# ZNXC.net
KiCad netlist of a schematic drawn in Altium Designer
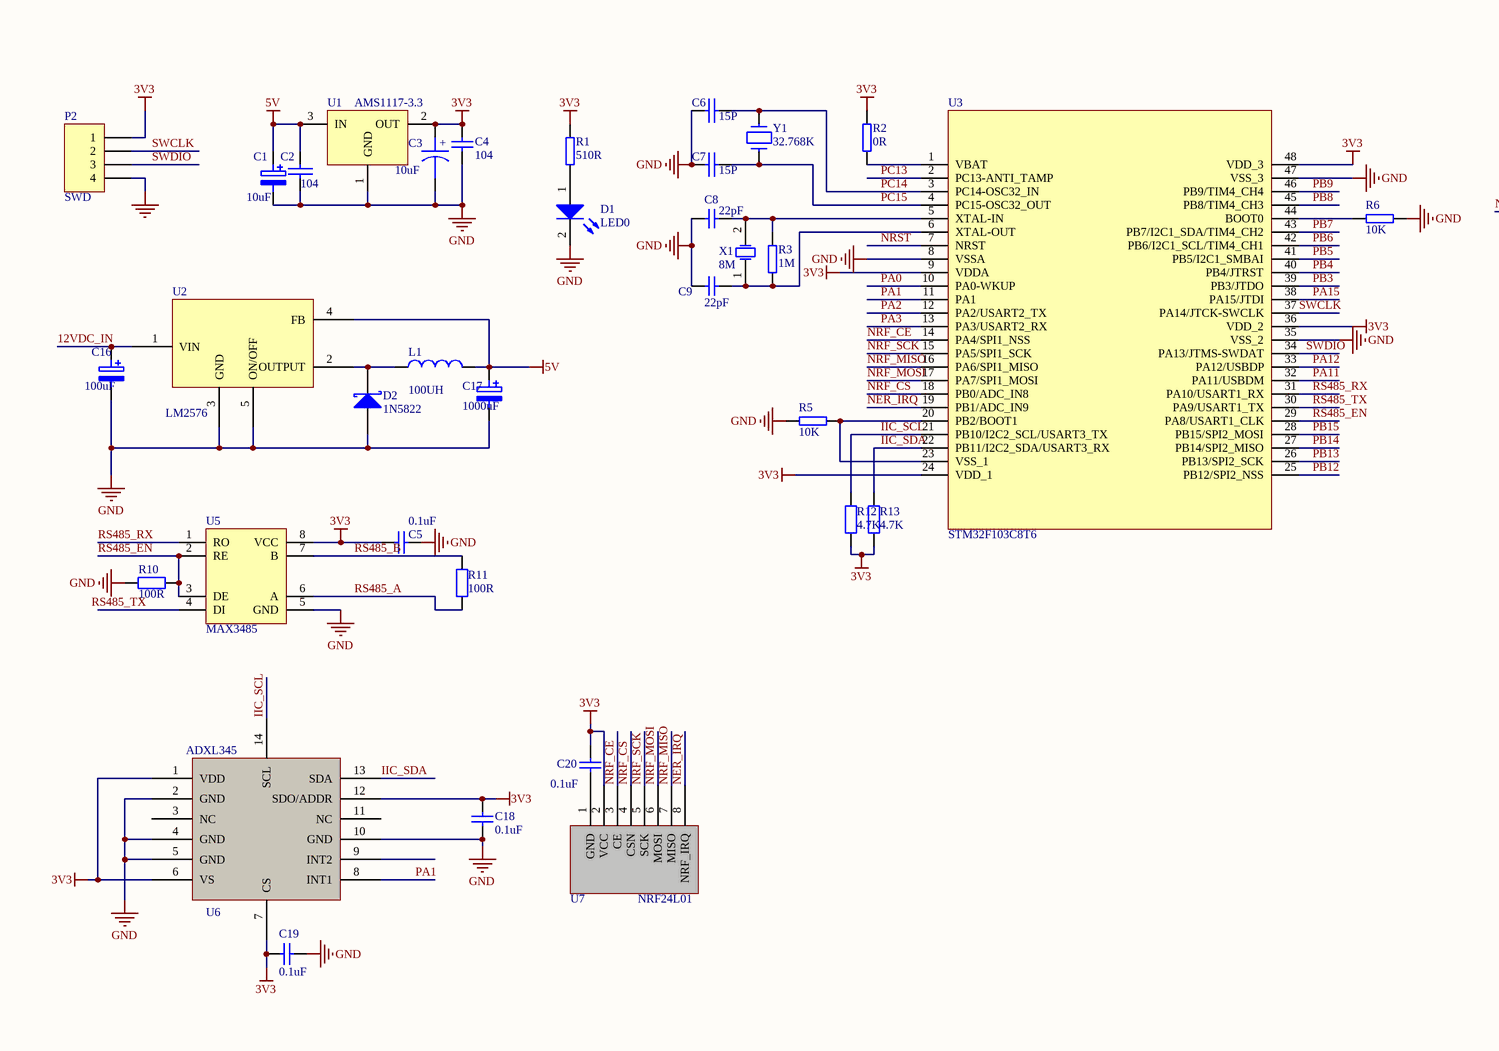
[diagram p0: ZNXC.SchDoc, left]
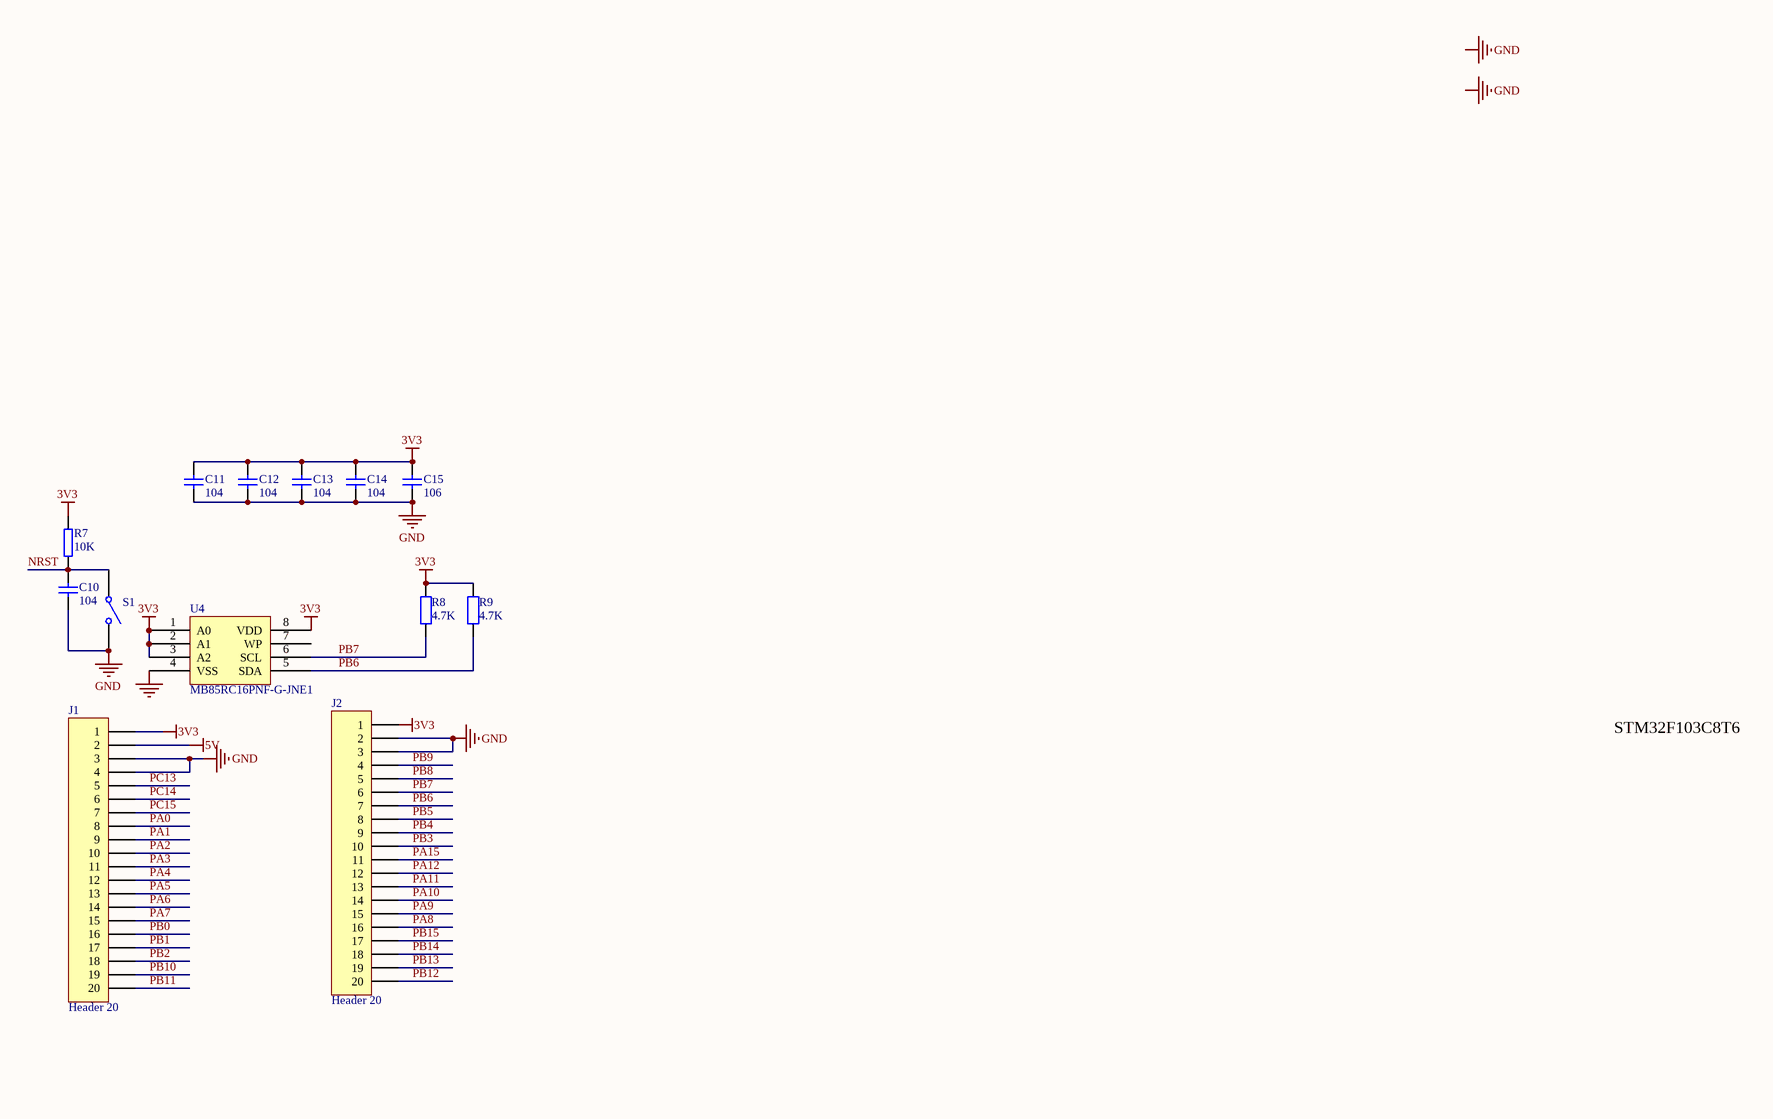
[diagram p1: ZNXC.SchDoc, right]

(export (version "E")
  (design (tool "Eeschema 10.0.6"))
  (components
    (comp (ref "C1") (value "10uF") (footprint "RC0805") (libsource (lib "*") (part "ELECTRO2")))
    (comp (ref "C2")
      (value "104")
      (footprint "RC0603")
      (description "Capacitor")
      (libsource (lib "") (part "CAP_1"))
    )
    (comp (ref "C3")
      (value "10uF")
      (footprint "RC0805")
      (description "Capacitor")
      (libsource (lib "*") (part "CAPACITOR POL"))
    )
    (comp (ref "C4")
      (value "104")
      (footprint "RC0603")
      (description "Capacitor")
      (fields (field (name "PUBLISHER") "Altium Limited"))
      (libsource (lib "*") (part "Cap"))
    )
    (comp (ref "C5")
      (value "0.1uF")
      (footprint "C0603")
      (description "Capacitor")
      (fields (field (name "Comment") "无源贴片电容") (field (name "PUBLISHER") "Altium Limited"))
      (libsource (lib "Miscellaneous Devices") (part "Cap"))
    )
    (comp (ref "C6") (value "15P") (footprint "RC0603") (libsource (lib "*") (part "CAP")))
    (comp (ref "C7") (value "15P") (footprint "RC0603") (libsource (lib "*") (part "CAP")))
    (comp (ref "C8")
      (value "22pF")
      (footprint "RC0603")
      (description "Capacitor")
      (fields (field (name "PUBLISHER") "ZL_A0OFFICE"))
      (libsource (lib "CommomDevices") (part "CAP1"))
    )
    (comp (ref "C9")
      (value "22pF")
      (footprint "RC0603")
      (description "Capacitor")
      (fields (field (name "PUBLISHER") "ZL_A0OFFICE"))
      (libsource (lib "CommomDevices") (part "CAP1"))
    )
    (comp (ref "C10")
      (value "104")
      (footprint "RC0603")
      (description "Capacitor")
      (fields (field (name "PUBLISHER") "ZL_A0OFFICE"))
      (libsource (lib "CommomDevices") (part "CAP1"))
    )
    (comp (ref "C11")
      (value "104")
      (footprint "RC0603")
      (description "Capacitor")
      (fields (field (name "PUBLISHER") "ZL_A0OFFICE"))
      (libsource (lib "CommomDevices") (part "CAP1"))
    )
    (comp (ref "C12")
      (value "104")
      (footprint "RC0603")
      (description "Capacitor")
      (fields (field (name "PUBLISHER") "ZL_A0OFFICE"))
      (libsource (lib "CommomDevices") (part "CAP1"))
    )
    (comp (ref "C13")
      (value "104")
      (footprint "RC0603")
      (description "Capacitor")
      (fields (field (name "PUBLISHER") "ZL_A0OFFICE"))
      (libsource (lib "CommomDevices") (part "CAP1"))
    )
    (comp (ref "C14")
      (value "104")
      (footprint "RC0603")
      (description "Capacitor")
      (fields (field (name "PUBLISHER") "ZL_A0OFFICE"))
      (libsource (lib "CommomDevices") (part "CAP1"))
    )
    (comp (ref "C15")
      (value "106")
      (footprint "RC0805")
      (description "Capacitor")
      (fields (field (name "PUBLISHER") "ZL_A0OFFICE"))
      (libsource (lib "CommomDevices") (part "CAP1"))
    )
    (comp (ref "C16") (value "100uF") (footprint "RC0805") (libsource (lib "*") (part "ELECTRO2")))
    (comp (ref "C17") (value "1000uF") (footprint "RC0805") (libsource (lib "*") (part "ELECTRO2")))
    (comp (ref "C18")
      (value "0.1uF")
      (footprint "C0603")
      (description "Capacitor")
      (fields (field (name "Comment") "无源贴片电容") (field (name "PUBLISHER") "Altium Limited"))
      (libsource (lib "Miscellaneous Devices") (part "Cap"))
    )
    (comp (ref "C19")
      (value "0.1uF")
      (footprint "C0603")
      (description "Capacitor")
      (fields (field (name "Comment") "无源贴片电容") (field (name "PUBLISHER") "Altium Limited"))
      (libsource (lib "Miscellaneous Devices") (part "Cap"))
    )
    (comp (ref "C20")
      (value "0.1uF")
      (footprint "C0603")
      (description "Capacitor")
      (fields (field (name "Comment") "无源贴片电容") (field (name "PUBLISHER") "Altium Limited"))
      (libsource (lib "Miscellaneous Devices") (part "Cap"))
    )
    (comp (ref "D1")
      (value "LED0")
      (footprint "LED0805")
      (description "Typical INFRARED GaAs LED")
      (libsource (lib "Miscellaneous Devices") (part "LED0"))
    )
    (comp (ref "D2")
      (value "1N5822")
      (footprint "DO-204AL")
      (description "Schottky Rectifier")
      (fields (field (name "PUBLISHER") "Altium Limited"))
      (libsource (lib "Miscellaneous Devices") (part "Diode 11DQ03"))
    )
    (comp (ref "J1")
      (value "Header 20")
      (footprint "HDR1X20")
      (description "Header, 20-Pin")
      (fields (field (name "PUBLISHER") "Altium Limited"))
      (libsource (lib "Miscellaneous Connectors") (part "Header 20"))
    )
    (comp (ref "J2")
      (value "Header 20")
      (footprint "HDR1X20")
      (description "Header, 20-Pin")
      (fields (field (name "PUBLISHER") "Altium Limited"))
      (libsource (lib "Miscellaneous Connectors") (part "Header 20"))
    )
    (comp (ref "L1")
      (value "100UH")
      (footprint "0402-A")
      (description "Inductor")
      (fields (field (name "PUBLISHER") "Altium Limited"))
      (libsource (lib "Miscellaneous Devices") (part "Inductor"))
    )
    (comp (ref "P2")
      (value "SWD")
      (footprint "XH2.54-4P")
      (description "Header, 4-Pin, Right Angle")
      (fields (field (name "PUBLISHER") "Altium Limited"))
      (libsource (lib "*") (part "Header 4H"))
    )
    (comp (ref "R1") (value "510R") (footprint "RC0603") (libsource (lib "ZIBO V2.0_Main") (part "R")))
    (comp (ref "R2") (value "0R") (footprint "RC0603") (libsource (lib "ZIBO V2.0_Main") (part "R")))
    (comp (ref "R3") (value "1M") (footprint "RC0603") (libsource (lib "ZIBO V2.0_Main") (part "R")))
    (comp (ref "R5") (value "10K") (footprint "RC0603") (libsource (lib "ZIBO V2.0_Main") (part "R")))
    (comp (ref "R6") (value "10K") (footprint "RC0603") (libsource (lib "ZIBO V2.0_Main") (part "R")))
    (comp (ref "R7") (value "10K") (footprint "RC0603") (libsource (lib "ZIBO V2.0_Main") (part "R")))
    (comp (ref "R8")
      (value "4.7K")
      (footprint "R0603")
      (description "贴片电阻 精度1%")
      (fields (field (name "PUBLISHER") "Altium Limited"))
      (libsource (lib "Miscellaneous Devices") (part "Res2"))
    )
    (comp (ref "R9")
      (value "4.7K")
      (footprint "R0603")
      (description "贴片电阻 精度1%")
      (fields (field (name "PUBLISHER") "Altium Limited"))
      (libsource (lib "Miscellaneous Devices") (part "Res2"))
    )
    (comp (ref "R10")
      (value "100R")
      (footprint "R0603")
      (description "Resistor")
      (fields (field (name "Comment") "贴片电阻 1%") (field (name "PUBLISHER") "Altium Limited"))
      (libsource (lib "*") (part "Res2"))
    )
    (comp (ref "R11")
      (value "100R")
      (footprint "R0603")
      (description "Resistor")
      (fields (field (name "Comment") "贴片电阻 1%") (field (name "PUBLISHER") "Altium Limited"))
      (libsource (lib "") (part "Res2_1"))
    )
    (comp (ref "R12")
      (value "4.7K")
      (footprint "R0603")
      (description "贴片电阻 精度1%")
      (fields (field (name "PUBLISHER") "Altium Limited"))
      (libsource (lib "Miscellaneous Devices") (part "Res2"))
    )
    (comp (ref "R13")
      (value "4.7K")
      (footprint "R0603")
      (description "贴片电阻 精度1%")
      (fields (field (name "PUBLISHER") "Altium Limited"))
      (libsource (lib "") (part "Res2_1"))
    )
    (comp (ref "S1")
      (value "SW-SPST")
      (footprint "SMT-KEY")
      (description "Single-Pole, Single-Throw Switch")
      (libsource (lib "Miscellaneous Devices") (part "SW-SPST"))
    )
    (comp (ref "U1")
      (value "AMS1117-3.3")
      (footprint "SOT223")
      (libsource (lib "Newcapec9263_Board_NEW") (part "LT1085CM-3.3"))
    )
    (comp (ref "U2") (value "LM2576") (libsource (lib "Schlib1") (part "LM2576")))
    (comp (ref "U3")
      (value "STM32F103C8T6")
      (footprint "LQFP48")
      (libsource (lib "STM32_Smart") (part "STM32F103C8T6"))
    )
    (comp (ref "U4")
      (value "MB85RC16PNF-G-JNE1")
      (footprint "SO-8")
      (description "EEPROM存储")
      (libsource (lib "*") (part "MB85RC16PNF-G-JNE1"))
    )
    (comp (ref "U5")
      (value "MAX3485")
      (footprint "SO-8")
      (description "485总线芯片")
      (libsource (lib "Fszhang") (part "SP3485"))
    )
    (comp (ref "U6") (value "ADXL345") (libsource (lib "Schlib1") (part "ADXL345")))
    (comp (ref "U7") (value "NRF24L01") (libsource (lib "Schlib1") (part "NRF24L01")))
    (comp (ref "X1")
      (value "8M")
      (footprint "SMD49S")
      (description "Crystal Oscillator")
      (fields (field (name "PUBLISHER") "ZL_A0OFFICE"))
      (libsource (lib "CommomDevices") (part "XTAL_SMD"))
    )
    (comp (ref "Y1")
      (value "32.768K")
      (footprint "JZ32768")
      (description "晶振")
      (libsource (lib "*") (part "CRYSTAL"))
    )
  )
  (nets
    (net (code "1") (name "/12VDC_IN") (class "Default")
      (node (ref "C16") (pin "1") (pintype "passive"))
      (node (ref "U2") (pin "1") (pinfunction "VIN_1") (pintype "passive"))
    )
    (net (code "2") (name "/IIC_SCL") (class "Default")
      (node (ref "R12") (pin "2") (pinfunction "2_2") (pintype "passive"))
      (node (ref "U3") (pin "21") (pinfunction "PB10/I2C2_SCL/USART3_TX_21") (pintype "passive"))
      (node (ref "U6") (pin "14") (pinfunction "SCL_14") (pintype "passive"))
    )
    (net (code "3") (name "/IIC_SDA") (class "Default")
      (node (ref "R13") (pin "1") (pinfunction "1_1") (pintype "passive"))
      (node (ref "U3") (pin "22") (pinfunction "PB11/I2C2_SDA/USART3_RX_22") (pintype "passive"))
      (node (ref "U6") (pin "13") (pinfunction "SDA_13") (pintype "passive"))
    )
    (net (code "4") (name "/NER_IRQ") (class "Default")
      (node (ref "U3") (pin "19") (pinfunction "PB1/ADC_IN9_19") (pintype "passive"))
      (node (ref "U7") (pin "8") (pinfunction "NRF_IRQ_8") (pintype "passive"))
    )
    (net (code "5") (name "/NRF_CE") (class "Default")
      (node (ref "U3") (pin "14") (pinfunction "PA4/SPI1_NSS_14") (pintype "passive"))
      (node (ref "U7") (pin "3") (pinfunction "CE_3") (pintype "passive"))
    )
    (net (code "6") (name "/NRF_CS") (class "Default")
      (node (ref "U3") (pin "18") (pinfunction "PB0/ADC_IN8_18") (pintype "passive"))
      (node (ref "U7") (pin "4") (pinfunction "CSN_4") (pintype "passive"))
    )
    (net (code "7") (name "/NRF_MISO") (class "Default")
      (node (ref "U3") (pin "16") (pinfunction "PA6/SPI1_MISO_16") (pintype "passive"))
      (node (ref "U7") (pin "7") (pinfunction "MISO_7") (pintype "passive"))
    )
    (net (code "8") (name "/NRF_MOSI") (class "Default")
      (node (ref "U3") (pin "17") (pinfunction "PA7/SPI1_MOSI_17") (pintype "passive"))
      (node (ref "U7") (pin "6") (pinfunction "MOSI_6") (pintype "passive"))
    )
    (net (code "9") (name "/NRF_SCK") (class "Default")
      (node (ref "U3") (pin "15") (pinfunction "PA5/SPI1_SCK_15") (pintype "passive"))
      (node (ref "U7") (pin "5") (pinfunction "SCK_5") (pintype "passive"))
    )
    (net (code "10") (name "/NRST") (class "Default")
      (node (ref "C10") (pin "1") (pinfunction "1_1") (pintype "passive"))
      (node (ref "R7") (pin "1") (pinfunction "1_1") (pintype "passive"))
      (node (ref "S1") (pin "1") (pinfunction "COMMON_1") (pintype "passive"))
      (node (ref "U3") (pin "7") (pinfunction "NRST_7") (pintype "passive"))
    )
    (net (code "11") (name "/PA0") (class "Default")
      (node (ref "J1") (pin "8") (pinfunction "8_8") (pintype "passive"))
      (node (ref "U3") (pin "10") (pinfunction "PA0-WKUP_10") (pintype "passive"))
    )
    (net (code "12") (name "/PA1") (class "Default")
      (node (ref "J1") (pin "9") (pinfunction "9_9") (pintype "passive"))
      (node (ref "U3") (pin "11") (pinfunction "PA1_11") (pintype "passive"))
      (node (ref "U6") (pin "8") (pinfunction "INT1_8") (pintype "passive"))
    )
    (net (code "13") (name "/PA2") (class "Default")
      (node (ref "J1") (pin "10") (pinfunction "10_10") (pintype "passive"))
      (node (ref "U3") (pin "12") (pinfunction "PA2/USART2_TX_12") (pintype "passive"))
    )
    (net (code "14") (name "/PA3") (class "Default")
      (node (ref "J1") (pin "11") (pinfunction "11_11") (pintype "passive"))
      (node (ref "U3") (pin "13") (pinfunction "PA3/USART2_RX_13") (pintype "passive"))
    )
    (net (code "15") (name "/PA4") (class "Default")
      (node (ref "J1") (pin "12") (pinfunction "12_12") (pintype "passive"))
    )
    (net (code "16") (name "/PA5") (class "Default")
      (node (ref "J1") (pin "13") (pinfunction "13_13") (pintype "passive"))
    )
    (net (code "17") (name "/PA6") (class "Default")
      (node (ref "J1") (pin "14") (pinfunction "14_14") (pintype "passive"))
    )
    (net (code "18") (name "/PA7") (class "Default")
      (node (ref "J1") (pin "15") (pinfunction "15_15") (pintype "passive"))
    )
    (net (code "19") (name "/PA8") (class "Default")
      (node (ref "J2") (pin "16") (pinfunction "16_16") (pintype "passive"))
    )
    (net (code "20") (name "/PA9") (class "Default")
      (node (ref "J2") (pin "15") (pinfunction "15_15") (pintype "passive"))
    )
    (net (code "21") (name "/PA10") (class "Default")
      (node (ref "J2") (pin "14") (pinfunction "14_14") (pintype "passive"))
    )
    (net (code "22") (name "/PA11") (class "Default")
      (node (ref "J2") (pin "13") (pinfunction "13_13") (pintype "passive"))
      (node (ref "U3") (pin "32") (pinfunction "PA11/USBDM_32") (pintype "passive"))
    )
    (net (code "23") (name "/PA12") (class "Default")
      (node (ref "J2") (pin "12") (pinfunction "12_12") (pintype "passive"))
      (node (ref "U3") (pin "33") (pinfunction "PA12/USBDP_33") (pintype "passive"))
    )
    (net (code "24") (name "/PA15") (class "Default")
      (node (ref "J2") (pin "11") (pinfunction "11_11") (pintype "passive"))
      (node (ref "U3") (pin "38") (pinfunction "PA15/JTDI_38") (pintype "passive"))
    )
    (net (code "25") (name "/PB0") (class "Default")
      (node (ref "J1") (pin "16") (pinfunction "16_16") (pintype "passive"))
    )
    (net (code "26") (name "/PB1") (class "Default")
      (node (ref "J1") (pin "17") (pinfunction "17_17") (pintype "passive"))
    )
    (net (code "27") (name "/PB2") (class "Default")
      (node (ref "J1") (pin "18") (pinfunction "18_18") (pintype "passive"))
    )
    (net (code "28") (name "/PB3") (class "Default")
      (node (ref "J2") (pin "10") (pinfunction "10_10") (pintype "passive"))
      (node (ref "U3") (pin "39") (pinfunction "PB3/JTDO_39") (pintype "passive"))
    )
    (net (code "29") (name "/PB4") (class "Default")
      (node (ref "J2") (pin "9") (pinfunction "9_9") (pintype "passive"))
      (node (ref "U3") (pin "40") (pinfunction "PB4/JTRST_40") (pintype "passive"))
    )
    (net (code "30") (name "/PB5") (class "Default")
      (node (ref "J2") (pin "8") (pinfunction "8_8") (pintype "passive"))
      (node (ref "U3") (pin "41") (pinfunction "PB5/I2C1_SMBAI_41") (pintype "passive"))
    )
    (net (code "31") (name "/PB6") (class "Default")
      (node (ref "J2") (pin "7") (pinfunction "7_7") (pintype "passive"))
      (node (ref "R9") (pin "1") (pinfunction "1_1") (pintype "passive"))
      (node (ref "U3") (pin "42") (pinfunction "PB6/I2C1_SCL/TIM4_CH1_42") (pintype "passive"))
      (node (ref "U4") (pin "5") (pinfunction "SDA_5") (pintype "passive"))
    )
    (net (code "32") (name "/PB7") (class "Default")
      (node (ref "J2") (pin "6") (pinfunction "6_6") (pintype "passive"))
      (node (ref "R8") (pin "1") (pinfunction "1_1") (pintype "passive"))
      (node (ref "U3") (pin "43") (pinfunction "PB7/I2C1_SDA/TIM4_CH2_43") (pintype "passive"))
      (node (ref "U4") (pin "6") (pinfunction "SCL_6") (pintype "passive"))
    )
    (net (code "33") (name "/PB8") (class "Default")
      (node (ref "J2") (pin "5") (pinfunction "5_5") (pintype "passive"))
      (node (ref "U3") (pin "45") (pinfunction "PB8/TIM4_CH3_45") (pintype "passive"))
    )
    (net (code "34") (name "/PB9") (class "Default")
      (node (ref "J2") (pin "4") (pinfunction "4_4") (pintype "passive"))
      (node (ref "U3") (pin "46") (pinfunction "PB9/TIM4_CH4_46") (pintype "passive"))
    )
    (net (code "35") (name "/PB10") (class "Default")
      (node (ref "J1") (pin "19") (pinfunction "19_19") (pintype "passive"))
    )
    (net (code "36") (name "/PB11") (class "Default")
      (node (ref "J1") (pin "20") (pinfunction "20_20") (pintype "passive"))
    )
    (net (code "37") (name "/PB12") (class "Default")
      (node (ref "J2") (pin "20") (pinfunction "20_20") (pintype "passive"))
      (node (ref "U3") (pin "25") (pinfunction "PB12/SPI2_NSS_25") (pintype "passive"))
    )
    (net (code "38") (name "/PB13") (class "Default")
      (node (ref "J2") (pin "19") (pinfunction "19_19") (pintype "passive"))
      (node (ref "U3") (pin "26") (pinfunction "PB13/SPI2_SCK_26") (pintype "passive"))
    )
    (net (code "39") (name "/PB14") (class "Default")
      (node (ref "J2") (pin "18") (pinfunction "18_18") (pintype "passive"))
      (node (ref "U3") (pin "27") (pinfunction "PB14/SPI2_MISO_27") (pintype "passive"))
    )
    (net (code "40") (name "/PB15") (class "Default")
      (node (ref "J2") (pin "17") (pinfunction "17_17") (pintype "passive"))
      (node (ref "U3") (pin "28") (pinfunction "PB15/SPI2_MOSI_28") (pintype "passive"))
    )
    (net (code "41") (name "/PC13") (class "Default")
      (node (ref "J1") (pin "5") (pinfunction "5_5") (pintype "passive"))
      (node (ref "U3") (pin "2") (pinfunction "PC13-ANTI_TAMP_2") (pintype "passive"))
    )
    (net (code "42") (name "/PC14") (class "Default")
      (node (ref "C6") (pin "2") (pintype "passive"))
      (node (ref "J1") (pin "6") (pinfunction "6_6") (pintype "passive"))
      (node (ref "U3") (pin "3") (pinfunction "PC14-OSC32_IN_3") (pintype "passive"))
      (node (ref "Y1") (pin "2") (pintype "passive"))
    )
    (net (code "43") (name "/PC15") (class "Default")
      (node (ref "C7") (pin "2") (pintype "passive"))
      (node (ref "J1") (pin "7") (pinfunction "7_7") (pintype "passive"))
      (node (ref "U3") (pin "4") (pinfunction "PC15-OSC32_OUT_4") (pintype "passive"))
      (node (ref "Y1") (pin "1") (pintype "passive"))
    )
    (net (code "44") (name "/RS485_A") (class "Default")
      (node (ref "R11") (pin "1") (pinfunction "1_1") (pintype "passive"))
      (node (ref "U5") (pin "6") (pinfunction "A_6") (pintype "passive"))
    )
    (net (code "45") (name "/RS485_B") (class "Default")
      (node (ref "R11") (pin "2") (pinfunction "2_2") (pintype "passive"))
      (node (ref "U5") (pin "7") (pinfunction "B_7") (pintype "passive"))
    )
    (net (code "46") (name "/RS485_EN") (class "Default")
      (node (ref "R10") (pin "2") (pinfunction "2_2") (pintype "passive"))
      (node (ref "U3") (pin "29") (pinfunction "PA8/USART1_CLK_29") (pintype "passive"))
      (node (ref "U5") (pin "2") (pinfunction "RE_2") (pintype "passive"))
      (node (ref "U5") (pin "3") (pinfunction "DE_3") (pintype "passive"))
    )
    (net (code "47") (name "/RS485_RX") (class "Default")
      (node (ref "U3") (pin "31") (pinfunction "PA10/USART1_RX_31") (pintype "passive"))
      (node (ref "U5") (pin "1") (pinfunction "RO_1") (pintype "passive"))
    )
    (net (code "48") (name "/RS485_TX") (class "Default")
      (node (ref "U3") (pin "30") (pinfunction "PA9/USART1_TX_30") (pintype "passive"))
    )
    (net (code "49") (name "/SWCLK") (class "Default")
      (node (ref "P2") (pin "2") (pinfunction "2_2") (pintype "passive"))
      (node (ref "U3") (pin "37") (pinfunction "PA14/JTCK-SWCLK_37") (pintype "passive"))
    )
    (net (code "50") (name "/SWDIO") (class "Default")
      (node (ref "P2") (pin "3") (pinfunction "3_3") (pintype "passive"))
      (node (ref "U3") (pin "34") (pinfunction "PA13/JTMS-SWDAT_34") (pintype "passive"))
    )
    (net (code "51") (name "3V3") (class "Default")
      (node (ref "C11") (pin "1") (pinfunction "1_1") (pintype "passive"))
      (node (ref "C12") (pin "1") (pinfunction "1_1") (pintype "passive"))
      (node (ref "C13") (pin "1") (pinfunction "1_1") (pintype "passive"))
      (node (ref "C14") (pin "1") (pinfunction "1_1") (pintype "passive"))
      (node (ref "C15") (pin "1") (pinfunction "1_1") (pintype "passive"))
      (node (ref "C18") (pin "1") (pinfunction "1_1") (pintype "passive"))
      (node (ref "C19") (pin "2") (pinfunction "2_2") (pintype "passive"))
      (node (ref "C20") (pin "1") (pinfunction "1_1") (pintype "passive"))
      (node (ref "C3") (pin "1") (pinfunction "1_1") (pintype "passive"))
      (node (ref "C4") (pin "1") (pinfunction "1_1") (pintype "passive"))
      (node (ref "C5") (pin "1") (pinfunction "1_1") (pintype "passive"))
      (node (ref "J1") (pin "1") (pinfunction "1_1") (pintype "passive"))
      (node (ref "J2") (pin "1") (pinfunction "1_1") (pintype "passive"))
      (node (ref "P2") (pin "1") (pinfunction "1_1") (pintype "passive"))
      (node (ref "R1") (pin "2") (pinfunction "2_2") (pintype "passive"))
      (node (ref "R12") (pin "1") (pinfunction "1_1") (pintype "passive"))
      (node (ref "R13") (pin "2") (pinfunction "2_2") (pintype "passive"))
      (node (ref "R2") (pin "2") (pinfunction "2_2") (pintype "passive"))
      (node (ref "R7") (pin "2") (pinfunction "2_2") (pintype "passive"))
      (node (ref "R8") (pin "2") (pinfunction "2_2") (pintype "passive"))
      (node (ref "R9") (pin "2") (pinfunction "2_2") (pintype "passive"))
      (node (ref "U1") (pin "2") (pinfunction "OUT_2") (pintype "passive"))
      (node (ref "U3") (pin "24") (pinfunction "VDD_1_24") (pintype "passive"))
      (node (ref "U3") (pin "36") (pinfunction "VDD_2_36") (pintype "passive"))
      (node (ref "U3") (pin "48") (pinfunction "VDD_3_48") (pintype "passive"))
      (node (ref "U3") (pin "9") (pinfunction "VDDA_9") (pintype "passive"))
      (node (ref "U4") (pin "1") (pinfunction "A0_1") (pintype "passive"))
      (node (ref "U4") (pin "2") (pinfunction "A1_2") (pintype "passive"))
      (node (ref "U4") (pin "3") (pinfunction "A2_3") (pintype "passive"))
      (node (ref "U4") (pin "8") (pinfunction "VDD_8") (pintype "passive"))
      (node (ref "U5") (pin "8") (pinfunction "VCC_8") (pintype "passive"))
      (node (ref "U6") (pin "1") (pinfunction "VDD_1") (pintype "passive"))
      (node (ref "U6") (pin "12") (pinfunction "SDO/ADDR_12") (pintype "passive"))
      (node (ref "U6") (pin "6") (pinfunction "VS_6") (pintype "passive"))
      (node (ref "U6") (pin "7") (pinfunction "CS_7") (pintype "passive"))
      (node (ref "U7") (pin "2") (pinfunction "VCC_2") (pintype "passive"))
    )
    (net (code "52") (name "5V") (class "Default")
      (node (ref "C1") (pin "1") (pintype "passive"))
      (node (ref "C17") (pin "1") (pintype "passive"))
      (node (ref "C2") (pin "1") (pinfunction "1_1") (pintype "passive"))
      (node (ref "J1") (pin "2") (pinfunction "2_2") (pintype "passive"))
      (node (ref "L1") (pin "2") (pinfunction "2_2") (pintype "passive"))
      (node (ref "U1") (pin "3") (pinfunction "IN_3") (pintype "passive"))
      (node (ref "U2") (pin "4") (pinfunction "FB_4") (pintype "passive"))
    )
    (net (code "53") (name "GND") (class "Default")
      (node (ref "C1") (pin "2") (pintype "passive"))
      (node (ref "C10") (pin "2") (pinfunction "2_2") (pintype "passive"))
      (node (ref "C11") (pin "2") (pinfunction "2_2") (pintype "passive"))
      (node (ref "C12") (pin "2") (pinfunction "2_2") (pintype "passive"))
      (node (ref "C13") (pin "2") (pinfunction "2_2") (pintype "passive"))
      (node (ref "C14") (pin "2") (pinfunction "2_2") (pintype "passive"))
      (node (ref "C15") (pin "2") (pinfunction "2_2") (pintype "passive"))
      (node (ref "C16") (pin "2") (pintype "passive"))
      (node (ref "C17") (pin "2") (pintype "passive"))
      (node (ref "C18") (pin "2") (pinfunction "2_2") (pintype "passive"))
      (node (ref "C19") (pin "1") (pinfunction "1_1") (pintype "passive"))
      (node (ref "C2") (pin "2") (pinfunction "2_2") (pintype "passive"))
      (node (ref "C3") (pin "2") (pinfunction "2_2") (pintype "passive"))
      (node (ref "C4") (pin "2") (pinfunction "2_2") (pintype "passive"))
      (node (ref "C5") (pin "2") (pinfunction "2_2") (pintype "passive"))
      (node (ref "C6") (pin "1") (pintype "passive"))
      (node (ref "C7") (pin "1") (pintype "passive"))
      (node (ref "C8") (pin "2") (pinfunction "2_2") (pintype "passive"))
      (node (ref "C9") (pin "2") (pinfunction "2_2") (pintype "passive"))
      (node (ref "D1") (pin "2") (pinfunction "K_2") (pintype "passive"))
      (node (ref "D2") (pin "1") (pinfunction "A_1") (pintype "passive"))
      (node (ref "J1") (pin "3") (pinfunction "3_3") (pintype "passive"))
      (node (ref "J1") (pin "4") (pinfunction "4_4") (pintype "passive"))
      (node (ref "J2") (pin "2") (pinfunction "2_2") (pintype "passive"))
      (node (ref "J2") (pin "3") (pinfunction "3_3") (pintype "passive"))
      (node (ref "P2") (pin "4") (pinfunction "4_4") (pintype "passive"))
      (node (ref "R10") (pin "1") (pinfunction "1_1") (pintype "passive"))
      (node (ref "R5") (pin "2") (pinfunction "2_2") (pintype "passive"))
      (node (ref "R6") (pin "1") (pinfunction "1_1") (pintype "passive"))
      (node (ref "S1") (pin "2") (pinfunction "NO_2") (pintype "passive"))
      (node (ref "U1") (pin "1") (pinfunction "GND_1") (pintype "passive"))
      (node (ref "U2") (pin "3") (pinfunction "GND_3") (pintype "passive"))
      (node (ref "U2") (pin "5") (pinfunction "ON/OFF_5") (pintype "passive"))
      (node (ref "U3") (pin "35") (pinfunction "VSS_2_35") (pintype "passive"))
      (node (ref "U3") (pin "47") (pinfunction "VSS_3_47") (pintype "passive"))
      (node (ref "U3") (pin "8") (pinfunction "VSSA_8") (pintype "passive"))
      (node (ref "U4") (pin "4") (pinfunction "VSS_4") (pintype "passive"))
      (node (ref "U5") (pin "5") (pinfunction "GND_5") (pintype "passive"))
      (node (ref "U6") (pin "10") (pinfunction "GND_10") (pintype "passive"))
      (node (ref "U6") (pin "2") (pinfunction "GND_2") (pintype "passive"))
      (node (ref "U6") (pin "4") (pinfunction "GND_4") (pintype "passive"))
      (node (ref "U6") (pin "5") (pinfunction "GND_5") (pintype "passive"))
    )
    (net (code "54") (name "Net-(D1-A)") (class "Default")
      (node (ref "D1") (pin "1") (pinfunction "A_1") (pintype "passive"))
      (node (ref "R1") (pin "1") (pinfunction "1_1") (pintype "passive"))
    )
    (net (code "55") (name "Net-(D2-K)") (class "Default")
      (node (ref "D2") (pin "2") (pinfunction "K_2") (pintype "passive"))
      (node (ref "L1") (pin "1") (pinfunction "1_1") (pintype "passive"))
      (node (ref "U2") (pin "2") (pinfunction "OUTPUT_2") (pintype "passive"))
    )
    (net (code "56") (name "Net-(U3-BOOT0)") (class "Default")
      (node (ref "R6") (pin "2") (pinfunction "2_2") (pintype "passive"))
      (node (ref "U3") (pin "44") (pinfunction "BOOT0_44") (pintype "passive"))
    )
    (net (code "57") (name "Net-(U3-PB2{slash}BOOT1)") (class "Default")
      (node (ref "R5") (pin "1") (pinfunction "1_1") (pintype "passive"))
      (node (ref "U3") (pin "20") (pinfunction "PB2/BOOT1_20") (pintype "passive"))
      (node (ref "U3") (pin "23") (pinfunction "VSS_1_23") (pintype "passive"))
    )
    (net (code "58") (name "Net-(U3-VBAT)") (class "Default")
      (node (ref "R2") (pin "1") (pinfunction "1_1") (pintype "passive"))
      (node (ref "U3") (pin "1") (pinfunction "VBAT_1") (pintype "passive"))
    )
    (net (code "59") (name "Net-(U3-XTAL-IN)") (class "Default")
      (node (ref "C8") (pin "1") (pinfunction "1_1") (pintype "passive"))
      (node (ref "R3") (pin "2") (pinfunction "2_2") (pintype "passive"))
      (node (ref "U3") (pin "5") (pinfunction "XTAL-IN_5") (pintype "passive"))
      (node (ref "X1") (pin "2") (pinfunction "2_2") (pintype "passive"))
    )
    (net (code "60") (name "Net-(U3-XTAL-OUT)") (class "Default")
      (node (ref "C9") (pin "1") (pinfunction "1_1") (pintype "passive"))
      (node (ref "R3") (pin "1") (pinfunction "1_1") (pintype "passive"))
      (node (ref "U3") (pin "6") (pinfunction "XTAL-OUT_6") (pintype "passive"))
      (node (ref "X1") (pin "1") (pinfunction "1_1") (pintype "passive"))
    )
    (net (code "61") (name "Net-(U7-GND)") (class "Default")
      (node (ref "C20") (pin "2") (pinfunction "2_2") (pintype "passive"))
      (node (ref "U7") (pin "1") (pinfunction "GND_1") (pintype "passive"))
    )
    (net (code "62") (name "unconnected-(U4-WP-Pad7)") (class "Default")
      (node (ref "U4") (pin "7") (pinfunction "WP_7") (pintype "passive"))
    )
    (net (code "63") (name "unconnected-(U5-DI-Pad4)") (class "Default")
      (node (ref "U5") (pin "4") (pinfunction "DI_4") (pintype "passive"))
    )
    (net (code "64") (name "unconnected-(U6-INT2-Pad9)") (class "Default")
      (node (ref "U6") (pin "9") (pinfunction "INT2_9") (pintype "passive"))
    )
    (net (code "65") (name "unconnected-(U6-NC-Pad3)") (class "Default")
      (node (ref "U6") (pin "3") (pinfunction "NC_3") (pintype "passive"))
    )
    (net (code "66") (name "unconnected-(U6-NC-Pad11)") (class "Default")
      (node (ref "U6") (pin "11") (pinfunction "NC_11") (pintype "passive"))
    )
  )
)
